# Heater_MOSFET_Channel.net
KiCad netlist of a schematic drawn in Altium Designer
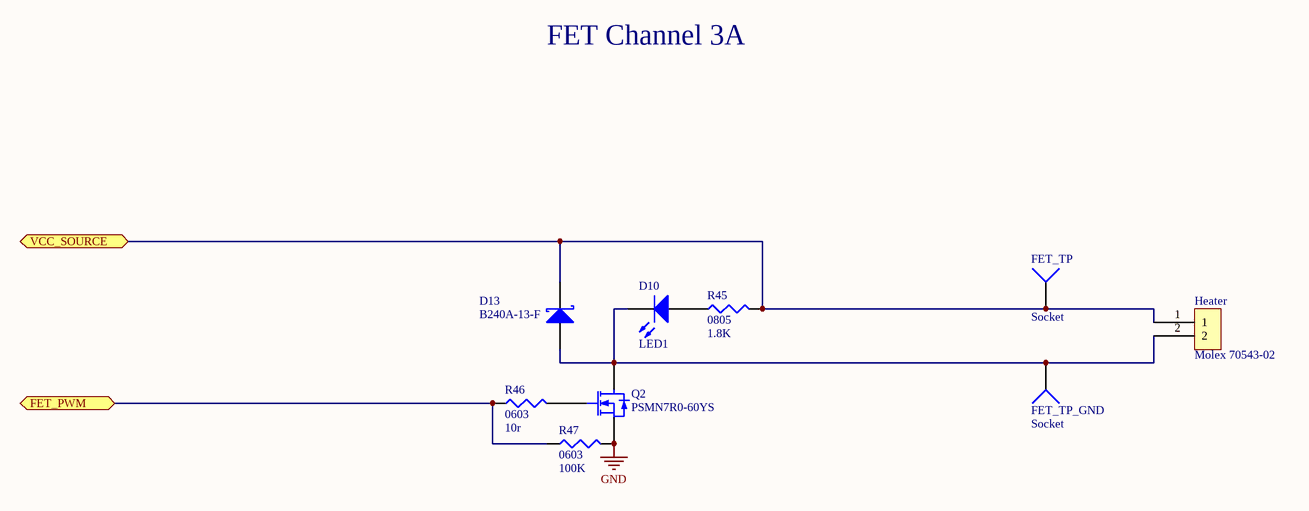
[diagram p0: Heater MOSFET Channel.SchDoc]

(export (version "E")
  (design (tool "Eeschema 10.0.6"))
  (components
    (comp (ref "D10")
      (value "LED1")
      (footprint "SM 0805 polarized")
      (description "Typical RED GaAs LED")
      (fields (field (name "PUBLISHER") "Altium Limited"))
      (libsource (lib "Miscellaneous Devices") (part "LED1"))
    )
    (comp (ref "D13")
      (value "B240A-13-F")
      (footprint "SMB")
      (description "Schottky Diode")
      (fields (field (name "PUBLISHER") "Altium Limited"))
      (libsource (lib "Miscellaneous Devices") (part "D Schottky"))
    )
    (comp (ref "FET_TP")
      (value "Socket")
      (footprint "PIN1")
      (fields (field (name "PUBLISHER") "Altium Limited"))
      (libsource (lib "Miscellaneous Connectors") (part "Socket"))
    )
    (comp (ref "FET_TP_GND")
      (value "Socket")
      (footprint "PIN1")
      (fields (field (name "PUBLISHER") "Altium Limited"))
      (libsource (lib "Miscellaneous Connectors") (part "Socket"))
    )
    (comp (ref "Heater")
      (value "Molex 70543-02")
      (footprint "70543-02")
      (libsource (lib "ZMBo Schematic Library") (part "Molex 70543-02"))
    )
    (comp (ref "Q2")
      (value "PSMN7R0-60YS")
      (footprint "PSMN7R0-60YS")
      (description "N-Channel MOSFET")
      (fields (field (name "PUBLISHER") "Altium Limited"))
      (libsource (lib "ZMBo Schematic Library") (part "Fairchild FDT439N"))
    )
    (comp (ref "R45")
      (value "0805")
      (footprint "SM 0805 - gap trimmed")
      (description "Resistor")
      (fields (field (name "ALTIUM_VALUE") "1.8K") (field (name "PUBLISHER") "Altium Limited"))
      (libsource (lib "Miscellaneous Devices") (part "Res3"))
    )
    (comp (ref "R46")
      (value "0603")
      (footprint "J1-0603")
      (description "Resistor")
      (fields (field (name "ALTIUM_VALUE") "10r") (field (name "PUBLISHER") "Altium Limited"))
      (libsource (lib "Miscellaneous Devices") (part "Res3"))
    )
    (comp (ref "R47")
      (value "0603")
      (footprint "J1-0603")
      (description "Resistor")
      (fields (field (name "ALTIUM_VALUE") "100K") (field (name "PUBLISHER") "Altium Limited"))
      (libsource (lib "Miscellaneous Devices") (part "Res3"))
    )
  )
  (nets
    (net (code "1") (name "/FET_PWM") (class "Default")
      (node (ref "R46") (pin "1") (pinfunction "1_1") (pintype "passive"))
      (node (ref "R47") (pin "1") (pinfunction "1_1") (pintype "passive"))
    )
    (net (code "2") (name "/VCC_SOURCE") (class "Default")
      (node (ref "D13") (pin "2") (pinfunction "K_2") (pintype "passive"))
      (node (ref "FET_TP") (pin "1") (pinfunction "1_1") (pintype "passive"))
      (node (ref "Heater") (pin "1") (pinfunction "1_1") (pintype "passive"))
      (node (ref "R45") (pin "2") (pinfunction "2_2") (pintype "passive"))
    )
    (net (code "3") (name "2") (class "Default")
      (node (ref "Q2") (pin "4") (pinfunction "D_4") (pintype "passive"))
    )
    (net (code "4") (name "GND") (class "Default")
      (node (ref "Q2") (pin "3") (pinfunction "S_3") (pintype "passive"))
      (node (ref "R47") (pin "2") (pinfunction "2_2") (pintype "passive"))
    )
    (net (code "5") (name "Net-(D10-A)") (class "Default")
      (node (ref "D10") (pin "1") (pinfunction "A_1") (pintype "passive"))
      (node (ref "R45") (pin "1") (pinfunction "1_1") (pintype "passive"))
    )
    (net (code "6") (name "Net-(D10-K)") (class "Default")
      (node (ref "D10") (pin "2") (pinfunction "K_2") (pintype "passive"))
      (node (ref "D13") (pin "1") (pinfunction "A_1") (pintype "passive"))
      (node (ref "FET_TP_GND") (pin "1") (pinfunction "1_1") (pintype "passive"))
      (node (ref "Heater") (pin "2") (pinfunction "2_2") (pintype "passive"))
      (node (ref "Q2") (pin "2") (pinfunction "D_2") (pintype "passive"))
    )
    (net (code "7") (name "Net-(Q2-G)") (class "Default")
      (node (ref "Q2") (pin "1") (pinfunction "G_1") (pintype "passive"))
      (node (ref "R46") (pin "2") (pinfunction "2_2") (pintype "passive"))
    )
  )
)
